# PCB_2d.net
KiCad netlist of a schematic drawn in EAGLE
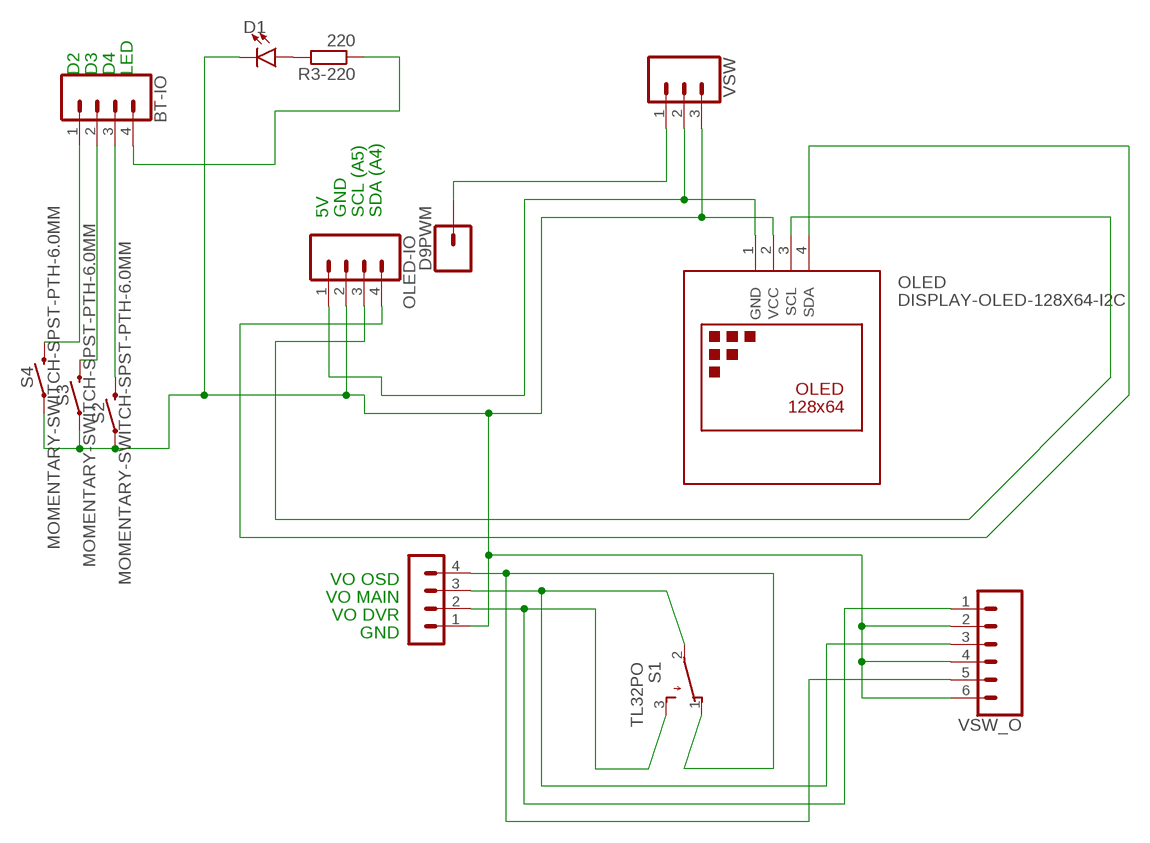
[diagram p0: schematic, sheet 1]

(export (version "E")
  (design (tool "Eeschema 10.0.6"))
  (components
    (comp (ref "BT-IO")
      (value "CONN_04")
      (footprint "eagle-import:1X04")
      (libsource (lib "eagle-import") (part "CONN_04"))
    )
    (comp (ref "D1")
      (value "LED3MM")
      (footprint "eagle-import:LED_3MM")
      (libsource (lib "eagle-import") (part "LED3MM"))
    )
    (comp (ref "D9PWM")
      (value "CONN_01")
      (footprint "eagle-import:1X01")
      (libsource (lib "eagle-import") (part "CONN_01"))
    )
    (comp (ref "IO3")
      (value "MA04-1")
      (footprint "eagle-import:MA04-1")
      (libsource (lib "eagle-import") (part "MA04-1"))
    )
    (comp (ref "OLED")
      (value "DISPLAY-OLED-128X64-I2C")
      (footprint "eagle-import:DISPLAY-OLED-128X64-I2C")
      (libsource (lib "eagle-import") (part "DISPLAY-OLED-128X64-I2C"))
    )
    (comp (ref "OLED-IO")
      (value "CONN_04")
      (footprint "eagle-import:1X04")
      (libsource (lib "eagle-import") (part "CONN_04"))
    )
    (comp (ref "R3-220")
      (value "220")
      (footprint "eagle-import:R1206")
      (libsource (lib "eagle-import") (part "R-EU_R1206"))
    )
    (comp (ref "S1")
      (value "TL32PO")
      (footprint "eagle-import:TL3XPO")
      (libsource (lib "eagle-import") (part "TL32PO"))
    )
    (comp (ref "S2")
      (value "MOMENTARY-SWITCH-SPST-PTH-6.0MM")
      (footprint "eagle-import:TACTILE_SWITCH_PTH_6.0MM")
      (libsource (lib "eagle-import") (part "MOMENTARY-SWITCH-SPST-PTH-6.0MM"))
    )
    (comp (ref "S3")
      (value "MOMENTARY-SWITCH-SPST-PTH-6.0MM")
      (footprint "eagle-import:TACTILE_SWITCH_PTH_6.0MM")
      (libsource (lib "eagle-import") (part "MOMENTARY-SWITCH-SPST-PTH-6.0MM"))
    )
    (comp (ref "S4")
      (value "MOMENTARY-SWITCH-SPST-PTH-6.0MM")
      (footprint "eagle-import:TACTILE_SWITCH_PTH_6.0MM")
      (libsource (lib "eagle-import") (part "MOMENTARY-SWITCH-SPST-PTH-6.0MM"))
    )
    (comp (ref "VSW")
      (value "CONN_03")
      (footprint "eagle-import:1X03")
      (libsource (lib "eagle-import") (part "CONN_03"))
    )
    (comp (ref "VSW_O")
      (value "CONN_06SILK_FEMALE_PTH")
      (footprint "eagle-import:1X06")
      (libsource (lib "eagle-import") (part "CONN_06SILK_FEMALE_PTH"))
    )
  )
  (nets
    (net (code "1") (name "Net-(BT-IO-Pad4)") (class "Default")
      (node (ref "BT-IO") (pin "4") (pinfunction "4_4") (pintype "passive"))
      (node (ref "R3-220") (pin "1") (pinfunction "1_1") (pintype "passive"))
    )
    (net (code "2") (name "Net-(D1-C)") (class "Default")
      (node (ref "D1") (pin "K") (pinfunction "C_K") (pintype "passive"))
      (node (ref "IO3") (pin "1") (pinfunction "1_1") (pintype "passive"))
      (node (ref "OLED") (pin "2") (pinfunction "VCC_2") (pintype "power_in"))
      (node (ref "OLED-IO") (pin "2") (pinfunction "2_2") (pintype "passive"))
      (node (ref "S2") (pin "1") (pinfunction "1_1") (pintype "passive"))
      (node (ref "S3") (pin "1") (pinfunction "1_1") (pintype "passive"))
      (node (ref "S4") (pin "1") (pinfunction "1_1") (pintype "passive"))
      (node (ref "VSW") (pin "3") (pinfunction "3_3") (pintype "passive"))
      (node (ref "VSW_O") (pin "2") (pinfunction "2_2") (pintype "passive"))
      (node (ref "VSW_O") (pin "4") (pinfunction "4_4") (pintype "passive"))
      (node (ref "VSW_O") (pin "6") (pinfunction "6_6") (pintype "passive"))
    )
    (net (code "3") (name "Net-(D1-PadA)") (class "Default")
      (node (ref "D1") (pin "A") (pinfunction "A_A") (pintype "passive"))
      (node (ref "R3-220") (pin "2") (pinfunction "2_2") (pintype "passive"))
    )
    (net (code "4") (name "Net-(D9PWM-Pad1)") (class "Default")
      (node (ref "D9PWM") (pin "1") (pinfunction "1_1") (pintype "passive"))
      (node (ref "VSW") (pin "1") (pinfunction "1_1") (pintype "passive"))
    )
    (net (code "5") (name "Net-(OLED-GND)") (class "Default")
      (node (ref "OLED") (pin "1") (pinfunction "GND_1") (pintype "power_in"))
      (node (ref "OLED-IO") (pin "1") (pinfunction "1_1") (pintype "passive"))
      (node (ref "VSW") (pin "2") (pinfunction "2_2") (pintype "passive"))
    )
    (net (code "6") (name "Net-(OLED-SCL)") (class "Default")
      (node (ref "OLED") (pin "3") (pinfunction "SCL_3") (pintype "bidirectional"))
      (node (ref "OLED-IO") (pin "3") (pinfunction "3_3") (pintype "passive"))
    )
    (net (code "7") (name "Net-(OLED-SDA)") (class "Default")
      (node (ref "OLED") (pin "4") (pinfunction "SDA_4") (pintype "bidirectional"))
      (node (ref "OLED-IO") (pin "4") (pinfunction "4_4") (pintype "passive"))
    )
    (net (code "8") (name "Net-(S1-O)") (class "Default")
      (node (ref "IO3") (pin "4") (pinfunction "4_4") (pintype "passive"))
      (node (ref "S1") (pin "1") (pinfunction "O_1") (pintype "passive"))
      (node (ref "VSW_O") (pin "5") (pinfunction "5_5") (pintype "passive"))
    )
    (net (code "9") (name "Net-(S1-P)") (class "Default")
      (node (ref "IO3") (pin "3") (pinfunction "3_3") (pintype "passive"))
      (node (ref "S1") (pin "2") (pinfunction "P_2") (pintype "passive"))
      (node (ref "VSW_O") (pin "3") (pinfunction "3_3") (pintype "passive"))
    )
    (net (code "10") (name "Net-(S1-S)") (class "Default")
      (node (ref "IO3") (pin "2") (pinfunction "2_2") (pintype "passive"))
      (node (ref "S1") (pin "3") (pinfunction "S_3") (pintype "passive"))
      (node (ref "VSW_O") (pin "1") (pinfunction "1_1") (pintype "passive"))
    )
    (net (code "11") (name "Net-(S2-2)") (class "Default")
      (node (ref "BT-IO") (pin "3") (pinfunction "3_3") (pintype "passive"))
      (node (ref "S2") (pin "3") (pinfunction "2_3") (pintype "passive"))
    )
    (net (code "12") (name "Net-(S3-2)") (class "Default")
      (node (ref "BT-IO") (pin "2") (pinfunction "2_2") (pintype "passive"))
      (node (ref "S3") (pin "3") (pinfunction "2_3") (pintype "passive"))
    )
    (net (code "13") (name "Net-(S4-2)") (class "Default")
      (node (ref "BT-IO") (pin "1") (pinfunction "1_1") (pintype "passive"))
      (node (ref "S4") (pin "3") (pinfunction "2_3") (pintype "passive"))
    )
  )
)
